# SoM.net
KiCad netlist of a schematic drawn in Altium Designer
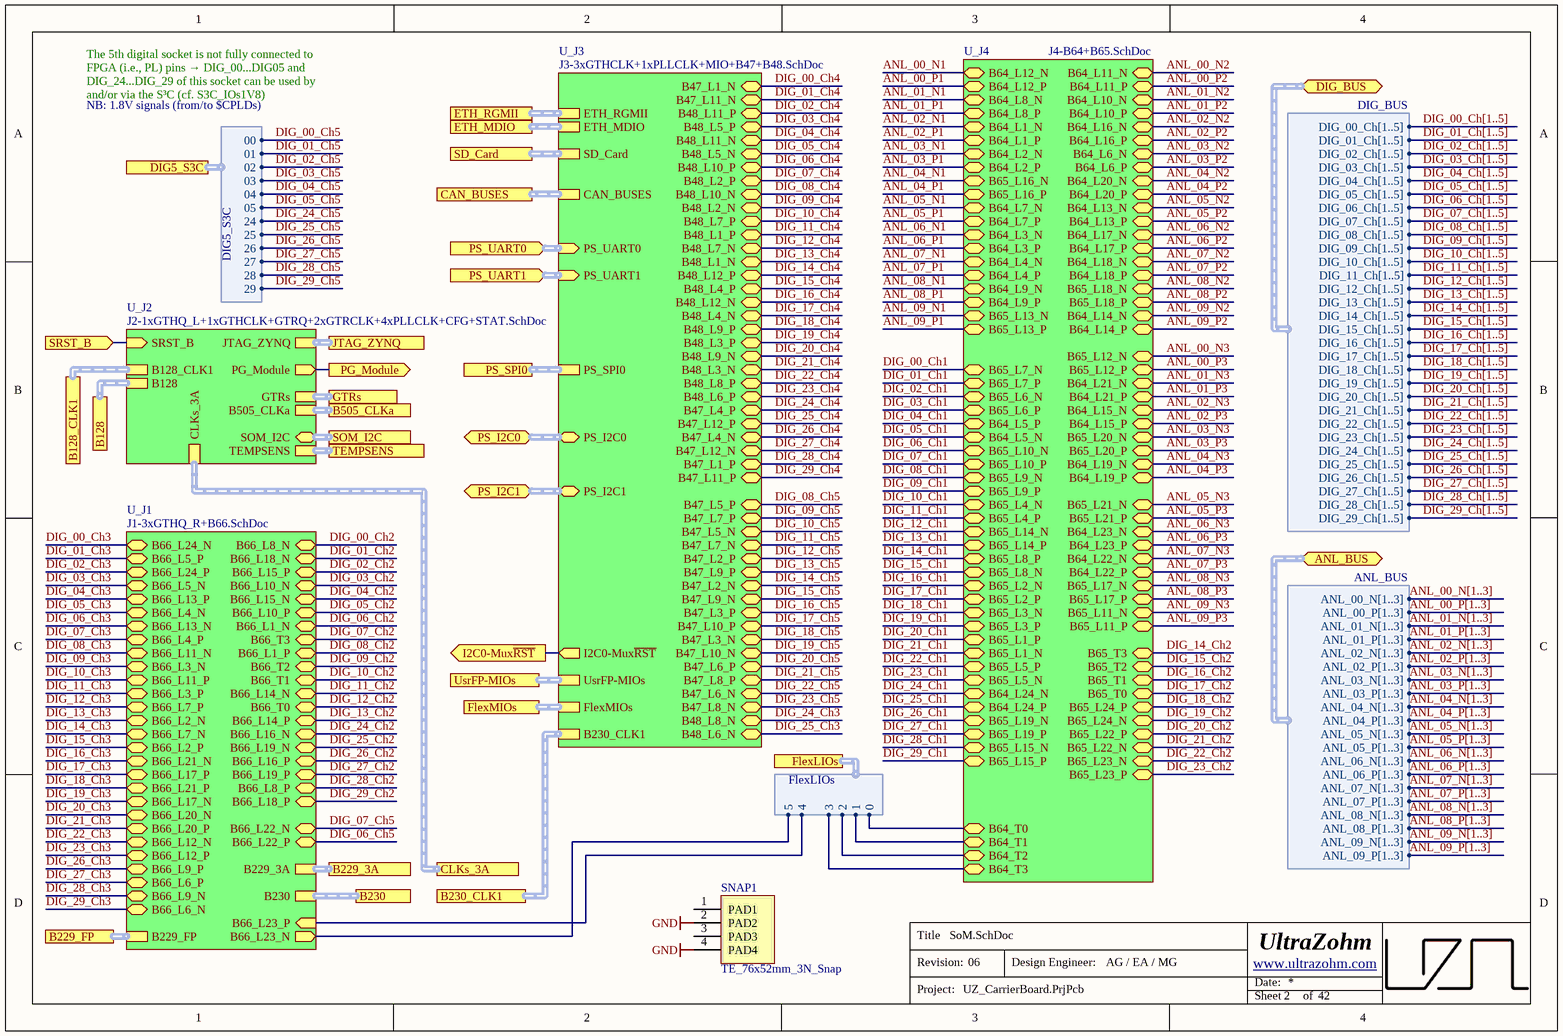
[diagram p0: SoM.SchDoc]

(export (version "E")
  (design (tool "Eeschema 10.0.6"))
  (components
    (comp (ref "SNAP1")
      (value "TE_76x52mm_3N_Snap")
      (footprint "TE_76x52mm_Snap")
      (description "TE0808 76x52mm Snap")
      (libsource (lib "TE") (part "TE_50x40mm_Snap"))
    )
  )
  (nets
    (net (code "299") (name "GND") (class "Default")
      (node (ref "SNAP1") (pin "2") (pinfunction "PAD2_2") (pintype "power_in"))
      (node (ref "SNAP1") (pin "4") (pinfunction "PAD4_4") (pintype "power_in"))
    )
    (net (code "300") (name "unconnected-(SNAP1-PAD1-Pad1)") (class "Default")
      (node (ref "SNAP1") (pin "1") (pinfunction "PAD1_1") (pintype "power_in"))
    )
    (net (code "301") (name "unconnected-(SNAP1-PAD3-Pad3)") (class "Default")
      (node (ref "SNAP1") (pin "3") (pinfunction "PAD3_3") (pintype "power_in"))
    )
  )
)
